# Backplane.net
KiCad netlist of a schematic drawn in EAGLE
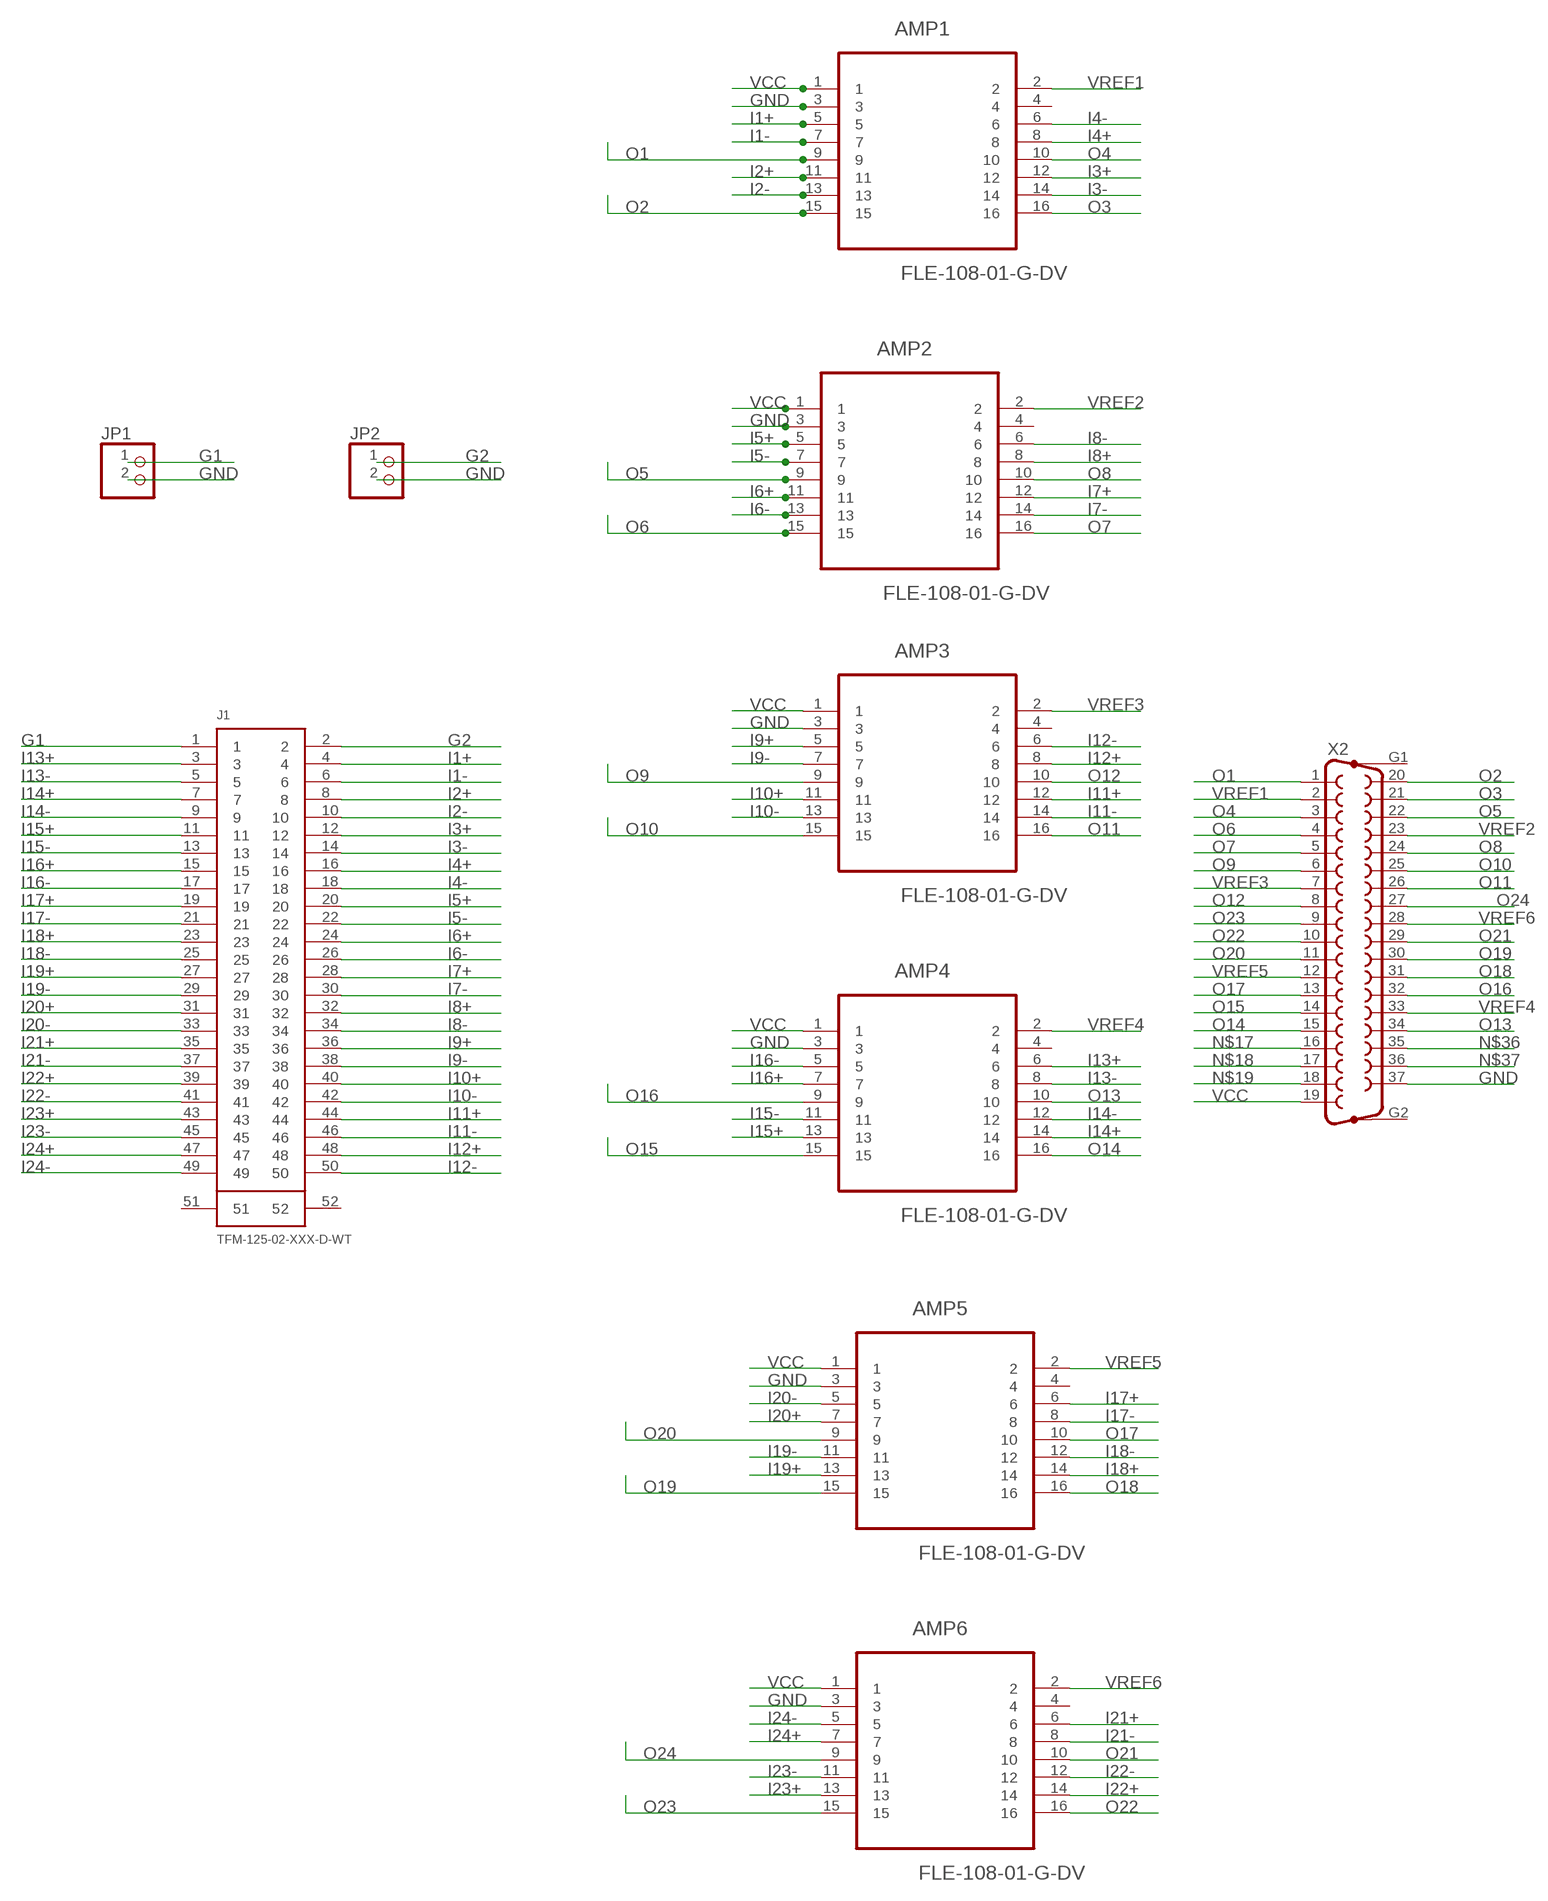
[diagram p0: schematic, sheet 1]

(export (version "E")
  (design (tool "Eeschema 10.0.6"))
  (components
    (comp (ref "AMP1")
      (value "FLE-108-01-G-DV")
      (footprint "eagle-import:SAMTEC_FLE-108-01-G-DV")
      (libsource (lib "eagle-import") (part "FLE-108-01-G-DV"))
    )
    (comp (ref "AMP2")
      (value "FLE-108-01-G-DV")
      (footprint "eagle-import:SAMTEC_FLE-108-01-G-DV")
      (libsource (lib "eagle-import") (part "FLE-108-01-G-DV"))
    )
    (comp (ref "AMP3")
      (value "FLE-108-01-G-DV")
      (footprint "eagle-import:SAMTEC_FLE-108-01-G-DV")
      (libsource (lib "eagle-import") (part "FLE-108-01-G-DV"))
    )
    (comp (ref "AMP4")
      (value "FLE-108-01-G-DV")
      (footprint "eagle-import:SAMTEC_FLE-108-01-G-DV")
      (libsource (lib "eagle-import") (part "FLE-108-01-G-DV"))
    )
    (comp (ref "AMP5")
      (value "FLE-108-01-G-DV")
      (footprint "eagle-import:SAMTEC_FLE-108-01-G-DV")
      (libsource (lib "eagle-import") (part "FLE-108-01-G-DV"))
    )
    (comp (ref "AMP6")
      (value "FLE-108-01-G-DV")
      (footprint "eagle-import:SAMTEC_FLE-108-01-G-DV")
      (libsource (lib "eagle-import") (part "FLE-108-01-G-DV"))
    )
    (comp (ref "J1")
      (value "TFM-125-02-XXX-D-WT")
      (footprint "eagle-import:TFM-125-02-XXX-D-WT")
      (libsource (lib "eagle-import") (part "TFM-125-02-XXX-D-WT"))
    )
    (comp (ref "JP1")
      (value "PINHD-1X2")
      (footprint "eagle-import:1X02")
      (libsource (lib "eagle-import") (part "PINHD-1X2"))
    )
    (comp (ref "JP2")
      (value "PINHD-1X2")
      (footprint "eagle-import:1X02")
      (libsource (lib "eagle-import") (part "PINHD-1X2"))
    )
    (comp (ref "X2")
      (value "F37HP")
      (footprint "eagle-import:F37HP")
      (libsource (lib "eagle-import") (part "F37HP"))
    )
  )
  (nets
    (net (code "1") (name "/G1") (class "Default")
      (node (ref "J1") (pin "1") (pinfunction "1_1") (pintype "bidirectional"))
      (node (ref "JP1") (pin "1") (pinfunction "1_1") (pintype "passive"))
    )
    (net (code "2") (name "/G2") (class "Default")
      (node (ref "J1") (pin "2") (pinfunction "2_2") (pintype "bidirectional"))
      (node (ref "JP2") (pin "1") (pinfunction "1_1") (pintype "passive"))
    )
    (net (code "3") (name "/GND") (class "Default")
      (node (ref "AMP1") (pin "3") (pinfunction "3_3") (pintype "passive"))
      (node (ref "AMP2") (pin "3") (pinfunction "3_3") (pintype "passive"))
      (node (ref "AMP3") (pin "3") (pinfunction "3_3") (pintype "passive"))
      (node (ref "AMP4") (pin "3") (pinfunction "3_3") (pintype "passive"))
      (node (ref "AMP5") (pin "3") (pinfunction "3_3") (pintype "passive"))
      (node (ref "AMP6") (pin "3") (pinfunction "3_3") (pintype "passive"))
      (node (ref "JP1") (pin "2") (pinfunction "2_2") (pintype "passive"))
      (node (ref "JP2") (pin "2") (pinfunction "2_2") (pintype "passive"))
      (node (ref "X2") (pin "37") (pinfunction "37_37") (pintype "passive"))
    )
    (net (code "4") (name "/I1+") (class "Default")
      (node (ref "AMP1") (pin "5") (pinfunction "5_5") (pintype "passive"))
      (node (ref "J1") (pin "4") (pinfunction "4_4") (pintype "bidirectional"))
    )
    (net (code "5") (name "/I1-") (class "Default")
      (node (ref "AMP1") (pin "7") (pinfunction "7_7") (pintype "passive"))
      (node (ref "J1") (pin "6") (pinfunction "6_6") (pintype "bidirectional"))
    )
    (net (code "6") (name "/I2+") (class "Default")
      (node (ref "AMP1") (pin "11") (pinfunction "11_11") (pintype "passive"))
      (node (ref "J1") (pin "8") (pinfunction "8_8") (pintype "bidirectional"))
    )
    (net (code "7") (name "/I2-") (class "Default")
      (node (ref "AMP1") (pin "13") (pinfunction "13_13") (pintype "passive"))
      (node (ref "J1") (pin "10") (pinfunction "10_10") (pintype "bidirectional"))
    )
    (net (code "8") (name "/I3+") (class "Default")
      (node (ref "AMP1") (pin "12") (pinfunction "12_12") (pintype "passive"))
      (node (ref "J1") (pin "12") (pinfunction "12_12") (pintype "bidirectional"))
    )
    (net (code "9") (name "/I3-") (class "Default")
      (node (ref "AMP1") (pin "14") (pinfunction "14_14") (pintype "passive"))
      (node (ref "J1") (pin "14") (pinfunction "14_14") (pintype "bidirectional"))
    )
    (net (code "10") (name "/I4+") (class "Default")
      (node (ref "AMP1") (pin "8") (pinfunction "8_8") (pintype "passive"))
      (node (ref "J1") (pin "16") (pinfunction "16_16") (pintype "bidirectional"))
    )
    (net (code "11") (name "/I4-") (class "Default")
      (node (ref "AMP1") (pin "6") (pinfunction "6_6") (pintype "passive"))
      (node (ref "J1") (pin "18") (pinfunction "18_18") (pintype "bidirectional"))
    )
    (net (code "12") (name "/I5+") (class "Default")
      (node (ref "AMP2") (pin "5") (pinfunction "5_5") (pintype "passive"))
      (node (ref "J1") (pin "20") (pinfunction "20_20") (pintype "bidirectional"))
    )
    (net (code "13") (name "/I5-") (class "Default")
      (node (ref "AMP2") (pin "7") (pinfunction "7_7") (pintype "passive"))
      (node (ref "J1") (pin "22") (pinfunction "22_22") (pintype "bidirectional"))
    )
    (net (code "14") (name "/I6+") (class "Default")
      (node (ref "AMP2") (pin "11") (pinfunction "11_11") (pintype "passive"))
      (node (ref "J1") (pin "24") (pinfunction "24_24") (pintype "bidirectional"))
    )
    (net (code "15") (name "/I6-") (class "Default")
      (node (ref "AMP2") (pin "13") (pinfunction "13_13") (pintype "passive"))
      (node (ref "J1") (pin "26") (pinfunction "26_26") (pintype "bidirectional"))
    )
    (net (code "16") (name "/I7+") (class "Default")
      (node (ref "AMP2") (pin "12") (pinfunction "12_12") (pintype "passive"))
      (node (ref "J1") (pin "28") (pinfunction "28_28") (pintype "bidirectional"))
    )
    (net (code "17") (name "/I7-") (class "Default")
      (node (ref "AMP2") (pin "14") (pinfunction "14_14") (pintype "passive"))
      (node (ref "J1") (pin "30") (pinfunction "30_30") (pintype "bidirectional"))
    )
    (net (code "18") (name "/I8+") (class "Default")
      (node (ref "AMP2") (pin "8") (pinfunction "8_8") (pintype "passive"))
      (node (ref "J1") (pin "32") (pinfunction "32_32") (pintype "bidirectional"))
    )
    (net (code "19") (name "/I8-") (class "Default")
      (node (ref "AMP2") (pin "6") (pinfunction "6_6") (pintype "passive"))
      (node (ref "J1") (pin "34") (pinfunction "34_34") (pintype "bidirectional"))
    )
    (net (code "20") (name "/I9+") (class "Default")
      (node (ref "AMP3") (pin "5") (pinfunction "5_5") (pintype "passive"))
      (node (ref "J1") (pin "36") (pinfunction "36_36") (pintype "bidirectional"))
    )
    (net (code "21") (name "/I9-") (class "Default")
      (node (ref "AMP3") (pin "7") (pinfunction "7_7") (pintype "passive"))
      (node (ref "J1") (pin "38") (pinfunction "38_38") (pintype "bidirectional"))
    )
    (net (code "22") (name "/I10+") (class "Default")
      (node (ref "AMP3") (pin "11") (pinfunction "11_11") (pintype "passive"))
      (node (ref "J1") (pin "40") (pinfunction "40_40") (pintype "bidirectional"))
    )
    (net (code "23") (name "/I10-") (class "Default")
      (node (ref "AMP3") (pin "13") (pinfunction "13_13") (pintype "passive"))
      (node (ref "J1") (pin "42") (pinfunction "42_42") (pintype "bidirectional"))
    )
    (net (code "24") (name "/I11+") (class "Default")
      (node (ref "AMP3") (pin "12") (pinfunction "12_12") (pintype "passive"))
      (node (ref "J1") (pin "44") (pinfunction "44_44") (pintype "bidirectional"))
    )
    (net (code "25") (name "/I11-") (class "Default")
      (node (ref "AMP3") (pin "14") (pinfunction "14_14") (pintype "passive"))
      (node (ref "J1") (pin "46") (pinfunction "46_46") (pintype "bidirectional"))
    )
    (net (code "26") (name "/I12+") (class "Default")
      (node (ref "AMP3") (pin "8") (pinfunction "8_8") (pintype "passive"))
      (node (ref "J1") (pin "48") (pinfunction "48_48") (pintype "bidirectional"))
    )
    (net (code "27") (name "/I12-") (class "Default")
      (node (ref "AMP3") (pin "6") (pinfunction "6_6") (pintype "passive"))
      (node (ref "J1") (pin "50") (pinfunction "50_50") (pintype "bidirectional"))
    )
    (net (code "28") (name "/I13+") (class "Default")
      (node (ref "AMP4") (pin "6") (pinfunction "6_6") (pintype "passive"))
      (node (ref "J1") (pin "3") (pinfunction "3_3") (pintype "bidirectional"))
    )
    (net (code "29") (name "/I13-") (class "Default")
      (node (ref "AMP4") (pin "8") (pinfunction "8_8") (pintype "passive"))
      (node (ref "J1") (pin "5") (pinfunction "5_5") (pintype "bidirectional"))
    )
    (net (code "30") (name "/I14+") (class "Default")
      (node (ref "AMP4") (pin "14") (pinfunction "14_14") (pintype "passive"))
      (node (ref "J1") (pin "7") (pinfunction "7_7") (pintype "bidirectional"))
    )
    (net (code "31") (name "/I14-") (class "Default")
      (node (ref "AMP4") (pin "12") (pinfunction "12_12") (pintype "passive"))
      (node (ref "J1") (pin "9") (pinfunction "9_9") (pintype "bidirectional"))
    )
    (net (code "32") (name "/I15+") (class "Default")
      (node (ref "AMP4") (pin "13") (pinfunction "13_13") (pintype "passive"))
      (node (ref "J1") (pin "11") (pinfunction "11_11") (pintype "bidirectional"))
    )
    (net (code "33") (name "/I15-") (class "Default")
      (node (ref "AMP4") (pin "11") (pinfunction "11_11") (pintype "passive"))
      (node (ref "J1") (pin "13") (pinfunction "13_13") (pintype "bidirectional"))
    )
    (net (code "34") (name "/I16+") (class "Default")
      (node (ref "AMP4") (pin "7") (pinfunction "7_7") (pintype "passive"))
      (node (ref "J1") (pin "15") (pinfunction "15_15") (pintype "bidirectional"))
    )
    (net (code "35") (name "/I16-") (class "Default")
      (node (ref "AMP4") (pin "5") (pinfunction "5_5") (pintype "passive"))
      (node (ref "J1") (pin "17") (pinfunction "17_17") (pintype "bidirectional"))
    )
    (net (code "36") (name "/I17+") (class "Default")
      (node (ref "AMP5") (pin "6") (pinfunction "6_6") (pintype "passive"))
      (node (ref "J1") (pin "19") (pinfunction "19_19") (pintype "bidirectional"))
    )
    (net (code "37") (name "/I17-") (class "Default")
      (node (ref "AMP5") (pin "8") (pinfunction "8_8") (pintype "passive"))
      (node (ref "J1") (pin "21") (pinfunction "21_21") (pintype "bidirectional"))
    )
    (net (code "38") (name "/I18+") (class "Default")
      (node (ref "AMP5") (pin "14") (pinfunction "14_14") (pintype "passive"))
      (node (ref "J1") (pin "23") (pinfunction "23_23") (pintype "bidirectional"))
    )
    (net (code "39") (name "/I18-") (class "Default")
      (node (ref "AMP5") (pin "12") (pinfunction "12_12") (pintype "passive"))
      (node (ref "J1") (pin "25") (pinfunction "25_25") (pintype "bidirectional"))
    )
    (net (code "40") (name "/I19+") (class "Default")
      (node (ref "AMP5") (pin "13") (pinfunction "13_13") (pintype "passive"))
      (node (ref "J1") (pin "27") (pinfunction "27_27") (pintype "bidirectional"))
    )
    (net (code "41") (name "/I19-") (class "Default")
      (node (ref "AMP5") (pin "11") (pinfunction "11_11") (pintype "passive"))
      (node (ref "J1") (pin "29") (pinfunction "29_29") (pintype "bidirectional"))
    )
    (net (code "42") (name "/I20+") (class "Default")
      (node (ref "AMP5") (pin "7") (pinfunction "7_7") (pintype "passive"))
      (node (ref "J1") (pin "31") (pinfunction "31_31") (pintype "bidirectional"))
    )
    (net (code "43") (name "/I20-") (class "Default")
      (node (ref "AMP5") (pin "5") (pinfunction "5_5") (pintype "passive"))
      (node (ref "J1") (pin "33") (pinfunction "33_33") (pintype "bidirectional"))
    )
    (net (code "44") (name "/I21+") (class "Default")
      (node (ref "AMP6") (pin "6") (pinfunction "6_6") (pintype "passive"))
      (node (ref "J1") (pin "35") (pinfunction "35_35") (pintype "bidirectional"))
    )
    (net (code "45") (name "/I21-") (class "Default")
      (node (ref "AMP6") (pin "8") (pinfunction "8_8") (pintype "passive"))
      (node (ref "J1") (pin "37") (pinfunction "37_37") (pintype "bidirectional"))
    )
    (net (code "46") (name "/I22+") (class "Default")
      (node (ref "AMP6") (pin "14") (pinfunction "14_14") (pintype "passive"))
      (node (ref "J1") (pin "39") (pinfunction "39_39") (pintype "bidirectional"))
    )
    (net (code "47") (name "/I22-") (class "Default")
      (node (ref "AMP6") (pin "12") (pinfunction "12_12") (pintype "passive"))
      (node (ref "J1") (pin "41") (pinfunction "41_41") (pintype "bidirectional"))
    )
    (net (code "48") (name "/I23+") (class "Default")
      (node (ref "AMP6") (pin "13") (pinfunction "13_13") (pintype "passive"))
      (node (ref "J1") (pin "43") (pinfunction "43_43") (pintype "bidirectional"))
    )
    (net (code "49") (name "/I23-") (class "Default")
      (node (ref "AMP6") (pin "11") (pinfunction "11_11") (pintype "passive"))
      (node (ref "J1") (pin "45") (pinfunction "45_45") (pintype "bidirectional"))
    )
    (net (code "50") (name "/I24+") (class "Default")
      (node (ref "AMP6") (pin "7") (pinfunction "7_7") (pintype "passive"))
      (node (ref "J1") (pin "47") (pinfunction "47_47") (pintype "bidirectional"))
    )
    (net (code "51") (name "/I24-") (class "Default")
      (node (ref "AMP6") (pin "5") (pinfunction "5_5") (pintype "passive"))
      (node (ref "J1") (pin "49") (pinfunction "49_49") (pintype "bidirectional"))
    )
    (net (code "52") (name "/N$17") (class "Default")
      (node (ref "X2") (pin "16") (pinfunction "16_16") (pintype "passive"))
    )
    (net (code "53") (name "/N$18") (class "Default")
      (node (ref "X2") (pin "17") (pinfunction "17_17") (pintype "passive"))
    )
    (net (code "54") (name "/N$19") (class "Default")
      (node (ref "X2") (pin "18") (pinfunction "18_18") (pintype "passive"))
    )
    (net (code "55") (name "/N$36") (class "Default")
      (node (ref "X2") (pin "35") (pinfunction "35_35") (pintype "passive"))
    )
    (net (code "56") (name "/N$37") (class "Default")
      (node (ref "X2") (pin "36") (pinfunction "36_36") (pintype "passive"))
    )
    (net (code "57") (name "/O1") (class "Default")
      (node (ref "AMP1") (pin "9") (pinfunction "9_9") (pintype "passive"))
      (node (ref "X2") (pin "1") (pinfunction "1_1") (pintype "passive"))
    )
    (net (code "58") (name "/O2") (class "Default")
      (node (ref "AMP1") (pin "15") (pinfunction "15_15") (pintype "passive"))
      (node (ref "X2") (pin "20") (pinfunction "20_20") (pintype "passive"))
    )
    (net (code "59") (name "/O3") (class "Default")
      (node (ref "AMP1") (pin "16") (pinfunction "16_16") (pintype "passive"))
      (node (ref "X2") (pin "21") (pinfunction "21_21") (pintype "passive"))
    )
    (net (code "60") (name "/O4") (class "Default")
      (node (ref "AMP1") (pin "10") (pinfunction "10_10") (pintype "passive"))
      (node (ref "X2") (pin "3") (pinfunction "3_3") (pintype "passive"))
    )
    (net (code "61") (name "/O5") (class "Default")
      (node (ref "AMP2") (pin "9") (pinfunction "9_9") (pintype "passive"))
      (node (ref "X2") (pin "22") (pinfunction "22_22") (pintype "passive"))
    )
    (net (code "62") (name "/O6") (class "Default")
      (node (ref "AMP2") (pin "15") (pinfunction "15_15") (pintype "passive"))
      (node (ref "X2") (pin "4") (pinfunction "4_4") (pintype "passive"))
    )
    (net (code "63") (name "/O7") (class "Default")
      (node (ref "AMP2") (pin "16") (pinfunction "16_16") (pintype "passive"))
      (node (ref "X2") (pin "5") (pinfunction "5_5") (pintype "passive"))
    )
    (net (code "64") (name "/O8") (class "Default")
      (node (ref "AMP2") (pin "10") (pinfunction "10_10") (pintype "passive"))
      (node (ref "X2") (pin "24") (pinfunction "24_24") (pintype "passive"))
    )
    (net (code "65") (name "/O9") (class "Default")
      (node (ref "AMP3") (pin "9") (pinfunction "9_9") (pintype "passive"))
      (node (ref "X2") (pin "6") (pinfunction "6_6") (pintype "passive"))
    )
    (net (code "66") (name "/O10") (class "Default")
      (node (ref "AMP3") (pin "15") (pinfunction "15_15") (pintype "passive"))
      (node (ref "X2") (pin "25") (pinfunction "25_25") (pintype "passive"))
    )
    (net (code "67") (name "/O11") (class "Default")
      (node (ref "AMP3") (pin "16") (pinfunction "16_16") (pintype "passive"))
      (node (ref "X2") (pin "26") (pinfunction "26_26") (pintype "passive"))
    )
    (net (code "68") (name "/O12") (class "Default")
      (node (ref "AMP3") (pin "10") (pinfunction "10_10") (pintype "passive"))
      (node (ref "X2") (pin "8") (pinfunction "8_8") (pintype "passive"))
    )
    (net (code "69") (name "/O13") (class "Default")
      (node (ref "AMP4") (pin "10") (pinfunction "10_10") (pintype "passive"))
      (node (ref "X2") (pin "34") (pinfunction "34_34") (pintype "passive"))
    )
    (net (code "70") (name "/O14") (class "Default")
      (node (ref "AMP4") (pin "16") (pinfunction "16_16") (pintype "passive"))
      (node (ref "X2") (pin "15") (pinfunction "15_15") (pintype "passive"))
    )
    (net (code "71") (name "/O15") (class "Default")
      (node (ref "AMP4") (pin "15") (pinfunction "15_15") (pintype "passive"))
      (node (ref "X2") (pin "14") (pinfunction "14_14") (pintype "passive"))
    )
    (net (code "72") (name "/O16") (class "Default")
      (node (ref "AMP4") (pin "9") (pinfunction "9_9") (pintype "passive"))
      (node (ref "X2") (pin "32") (pinfunction "32_32") (pintype "passive"))
    )
    (net (code "73") (name "/O17") (class "Default")
      (node (ref "AMP5") (pin "10") (pinfunction "10_10") (pintype "passive"))
      (node (ref "X2") (pin "13") (pinfunction "13_13") (pintype "passive"))
    )
    (net (code "74") (name "/O18") (class "Default")
      (node (ref "AMP5") (pin "16") (pinfunction "16_16") (pintype "passive"))
      (node (ref "X2") (pin "31") (pinfunction "31_31") (pintype "passive"))
    )
    (net (code "75") (name "/O19") (class "Default")
      (node (ref "AMP5") (pin "15") (pinfunction "15_15") (pintype "passive"))
      (node (ref "X2") (pin "30") (pinfunction "30_30") (pintype "passive"))
    )
    (net (code "76") (name "/O20") (class "Default")
      (node (ref "AMP5") (pin "9") (pinfunction "9_9") (pintype "passive"))
      (node (ref "X2") (pin "11") (pinfunction "11_11") (pintype "passive"))
    )
    (net (code "77") (name "/O21") (class "Default")
      (node (ref "AMP6") (pin "10") (pinfunction "10_10") (pintype "passive"))
      (node (ref "X2") (pin "29") (pinfunction "29_29") (pintype "passive"))
    )
    (net (code "78") (name "/O22") (class "Default")
      (node (ref "AMP6") (pin "16") (pinfunction "16_16") (pintype "passive"))
      (node (ref "X2") (pin "10") (pinfunction "10_10") (pintype "passive"))
    )
    (net (code "79") (name "/O23") (class "Default")
      (node (ref "AMP6") (pin "15") (pinfunction "15_15") (pintype "passive"))
      (node (ref "X2") (pin "9") (pinfunction "9_9") (pintype "passive"))
    )
    (net (code "80") (name "/O24") (class "Default")
      (node (ref "AMP6") (pin "9") (pinfunction "9_9") (pintype "passive"))
      (node (ref "X2") (pin "27") (pinfunction "27_27") (pintype "passive"))
    )
    (net (code "81") (name "/VCC") (class "Default")
      (node (ref "AMP1") (pin "1") (pinfunction "1_1") (pintype "passive"))
      (node (ref "AMP2") (pin "1") (pinfunction "1_1") (pintype "passive"))
      (node (ref "AMP3") (pin "1") (pinfunction "1_1") (pintype "passive"))
      (node (ref "AMP4") (pin "1") (pinfunction "1_1") (pintype "passive"))
      (node (ref "AMP5") (pin "1") (pinfunction "1_1") (pintype "passive"))
      (node (ref "AMP6") (pin "1") (pinfunction "1_1") (pintype "passive"))
      (node (ref "X2") (pin "19") (pinfunction "19_19") (pintype "passive"))
    )
    (net (code "82") (name "/VREF1") (class "Default")
      (node (ref "AMP1") (pin "2") (pinfunction "2_2") (pintype "passive"))
      (node (ref "X2") (pin "2") (pinfunction "2_2") (pintype "passive"))
    )
    (net (code "83") (name "/VREF2") (class "Default")
      (node (ref "AMP2") (pin "2") (pinfunction "2_2") (pintype "passive"))
      (node (ref "X2") (pin "23") (pinfunction "23_23") (pintype "passive"))
    )
    (net (code "84") (name "/VREF3") (class "Default")
      (node (ref "AMP3") (pin "2") (pinfunction "2_2") (pintype "passive"))
      (node (ref "X2") (pin "7") (pinfunction "7_7") (pintype "passive"))
    )
    (net (code "85") (name "/VREF4") (class "Default")
      (node (ref "AMP4") (pin "2") (pinfunction "2_2") (pintype "passive"))
      (node (ref "X2") (pin "33") (pinfunction "33_33") (pintype "passive"))
    )
    (net (code "86") (name "/VREF5") (class "Default")
      (node (ref "AMP5") (pin "2") (pinfunction "2_2") (pintype "passive"))
      (node (ref "X2") (pin "12") (pinfunction "12_12") (pintype "passive"))
    )
    (net (code "87") (name "/VREF6") (class "Default")
      (node (ref "AMP6") (pin "2") (pinfunction "2_2") (pintype "passive"))
      (node (ref "X2") (pin "28") (pinfunction "28_28") (pintype "passive"))
    )
    (net (code "88") (name "unconnected-(AMP1-Pad4)") (class "Default")
      (node (ref "AMP1") (pin "4") (pinfunction "4_4") (pintype "passive"))
    )
    (net (code "89") (name "unconnected-(AMP2-Pad4)") (class "Default")
      (node (ref "AMP2") (pin "4") (pinfunction "4_4") (pintype "passive"))
    )
    (net (code "90") (name "unconnected-(AMP3-Pad4)") (class "Default")
      (node (ref "AMP3") (pin "4") (pinfunction "4_4") (pintype "passive"))
    )
    (net (code "91") (name "unconnected-(AMP4-Pad4)") (class "Default")
      (node (ref "AMP4") (pin "4") (pinfunction "4_4") (pintype "passive"))
    )
    (net (code "92") (name "unconnected-(AMP5-Pad4)") (class "Default")
      (node (ref "AMP5") (pin "4") (pinfunction "4_4") (pintype "passive"))
    )
    (net (code "93") (name "unconnected-(AMP6-Pad4)") (class "Default")
      (node (ref "AMP6") (pin "4") (pinfunction "4_4") (pintype "passive"))
    )
    (net (code "94") (name "unconnected-(J1-Pad51)") (class "Default")
      (node (ref "J1") (pin "51") (pinfunction "51_51") (pintype "bidirectional"))
    )
    (net (code "95") (name "unconnected-(J1-Pad52)") (class "Default")
      (node (ref "J1") (pin "52") (pinfunction "52_52") (pintype "bidirectional"))
    )
    (net (code "96") (name "unconnected-(X2-PadG1)") (class "Default")
      (node (ref "X2") (pin "G1") (pinfunction "G1_G1") (pintype "passive"))
    )
    (net (code "97") (name "unconnected-(X2-PadG2)") (class "Default")
      (node (ref "X2") (pin "G2") (pinfunction "G2_G2") (pintype "passive"))
    )
  )
)
